# FPC_ES_TO_PD.net
KiCad netlist of a schematic drawn in Altium Designer
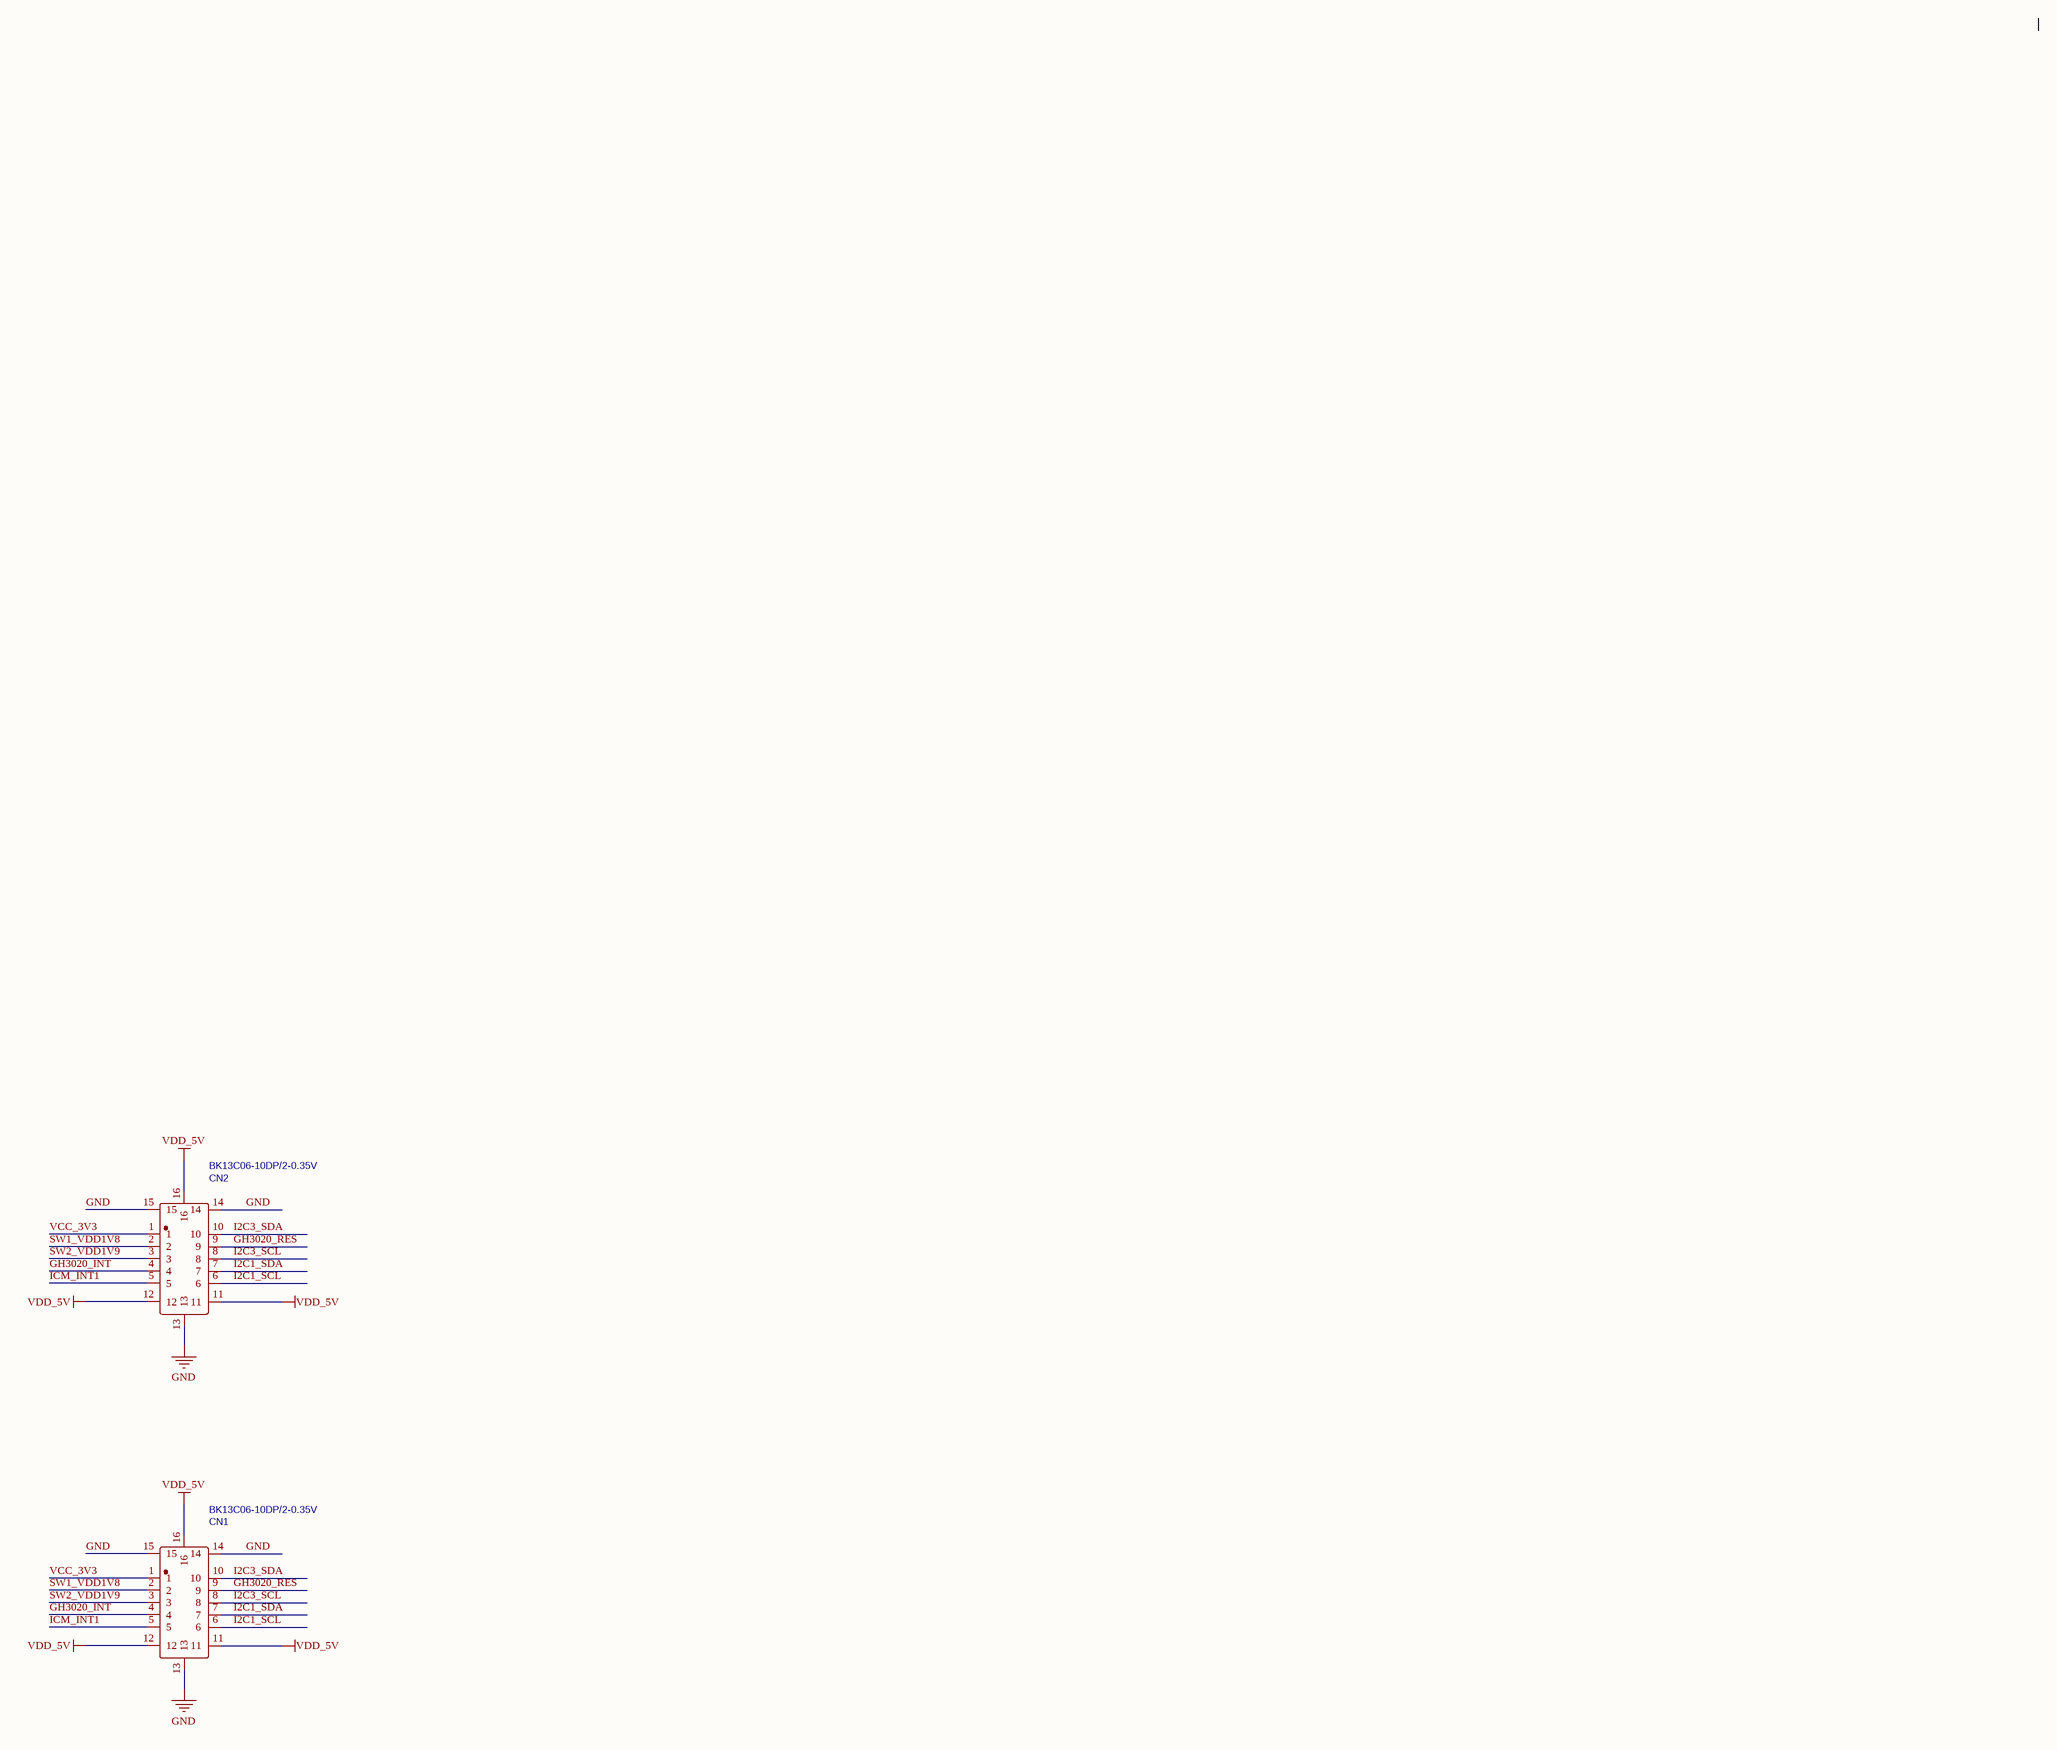
[diagram p0: FPC_ES_TO_PD.SchDoc]

(export (version "E")
  (design (tool "Eeschema 10.0.6"))
  (components
    (comp (ref "CN1")
      (value "BK13C06-10DP/2-0.35V")
      (footprint "smart bracelet:CONN-SMD_10P-P0.35_BK13C06-10DP")
      (fields (field (name "CONTRIBUTOR") "lcsc"))
      (libsource (lib "smart bracelet") (part "10pin_dp_BK13C06-10DP/2-0.35V"))
    )
    (comp (ref "CN2")
      (value "BK13C06-10DP/2-0.35V")
      (footprint "smart bracelet:CONN-SMD_10P-P0.35_BK13C06-10DP")
      (fields (field (name "CONTRIBUTOR") "lcsc"))
      (libsource (lib "smart bracelet") (part "10pin_dp_BK13C06-10DP/2-0.35V"))
    )
  )
  (nets
    (net (code "1") (name "/GH3020_INT") (class "Default")
      (node (ref "CN1") (pin "4") (pinfunction "4_4") (pintype "passive"))
      (node (ref "CN2") (pin "4") (pinfunction "4_4") (pintype "passive"))
    )
    (net (code "2") (name "/GH3020_RES") (class "Default")
      (node (ref "CN1") (pin "9") (pinfunction "9_9") (pintype "passive"))
      (node (ref "CN2") (pin "9") (pinfunction "9_9") (pintype "passive"))
    )
    (net (code "3") (name "/I2C1_SCL") (class "Default")
      (node (ref "CN1") (pin "6") (pinfunction "6_6") (pintype "passive"))
      (node (ref "CN2") (pin "6") (pinfunction "6_6") (pintype "passive"))
    )
    (net (code "4") (name "/I2C1_SDA") (class "Default")
      (node (ref "CN1") (pin "7") (pinfunction "7_7") (pintype "passive"))
      (node (ref "CN2") (pin "7") (pinfunction "7_7") (pintype "passive"))
    )
    (net (code "5") (name "/I2C3_SCL") (class "Default")
      (node (ref "CN1") (pin "8") (pinfunction "8_8") (pintype "passive"))
      (node (ref "CN2") (pin "8") (pinfunction "8_8") (pintype "passive"))
    )
    (net (code "6") (name "/I2C3_SDA") (class "Default")
      (node (ref "CN1") (pin "10") (pinfunction "10_10") (pintype "passive"))
      (node (ref "CN2") (pin "10") (pinfunction "10_10") (pintype "passive"))
    )
    (net (code "7") (name "/ICM_INT1") (class "Default")
      (node (ref "CN1") (pin "5") (pinfunction "5_5") (pintype "passive"))
      (node (ref "CN2") (pin "5") (pinfunction "5_5") (pintype "passive"))
    )
    (net (code "8") (name "/SW1_VDD1V8") (class "Default")
      (node (ref "CN1") (pin "2") (pinfunction "2_2") (pintype "passive"))
      (node (ref "CN2") (pin "2") (pinfunction "2_2") (pintype "passive"))
    )
    (net (code "9") (name "/SW2_VDD1V9") (class "Default")
      (node (ref "CN1") (pin "3") (pinfunction "3_3") (pintype "passive"))
      (node (ref "CN2") (pin "3") (pinfunction "3_3") (pintype "passive"))
    )
    (net (code "10") (name "/VCC_3V3") (class "Default")
      (node (ref "CN1") (pin "1") (pinfunction "1_1") (pintype "passive"))
      (node (ref "CN2") (pin "1") (pinfunction "1_1") (pintype "passive"))
    )
    (net (code "11") (name "GND") (class "Default")
      (node (ref "CN1") (pin "13") (pinfunction "13_13") (pintype "passive"))
      (node (ref "CN1") (pin "14") (pinfunction "14_14") (pintype "passive"))
      (node (ref "CN1") (pin "15") (pinfunction "15_15") (pintype "passive"))
      (node (ref "CN2") (pin "13") (pinfunction "13_13") (pintype "passive"))
      (node (ref "CN2") (pin "14") (pinfunction "14_14") (pintype "passive"))
      (node (ref "CN2") (pin "15") (pinfunction "15_15") (pintype "passive"))
    )
    (net (code "12") (name "VDD_5V") (class "Default")
      (node (ref "CN1") (pin "11") (pinfunction "11_11") (pintype "passive"))
      (node (ref "CN1") (pin "12") (pinfunction "12_12") (pintype "passive"))
      (node (ref "CN1") (pin "16") (pinfunction "16_16") (pintype "passive"))
      (node (ref "CN2") (pin "11") (pinfunction "11_11") (pintype "passive"))
      (node (ref "CN2") (pin "12") (pinfunction "12_12") (pintype "passive"))
      (node (ref "CN2") (pin "16") (pinfunction "16_16") (pintype "passive"))
    )
  )
)
